# strobo.net
KiCad netlist of a schematic drawn in EAGLE
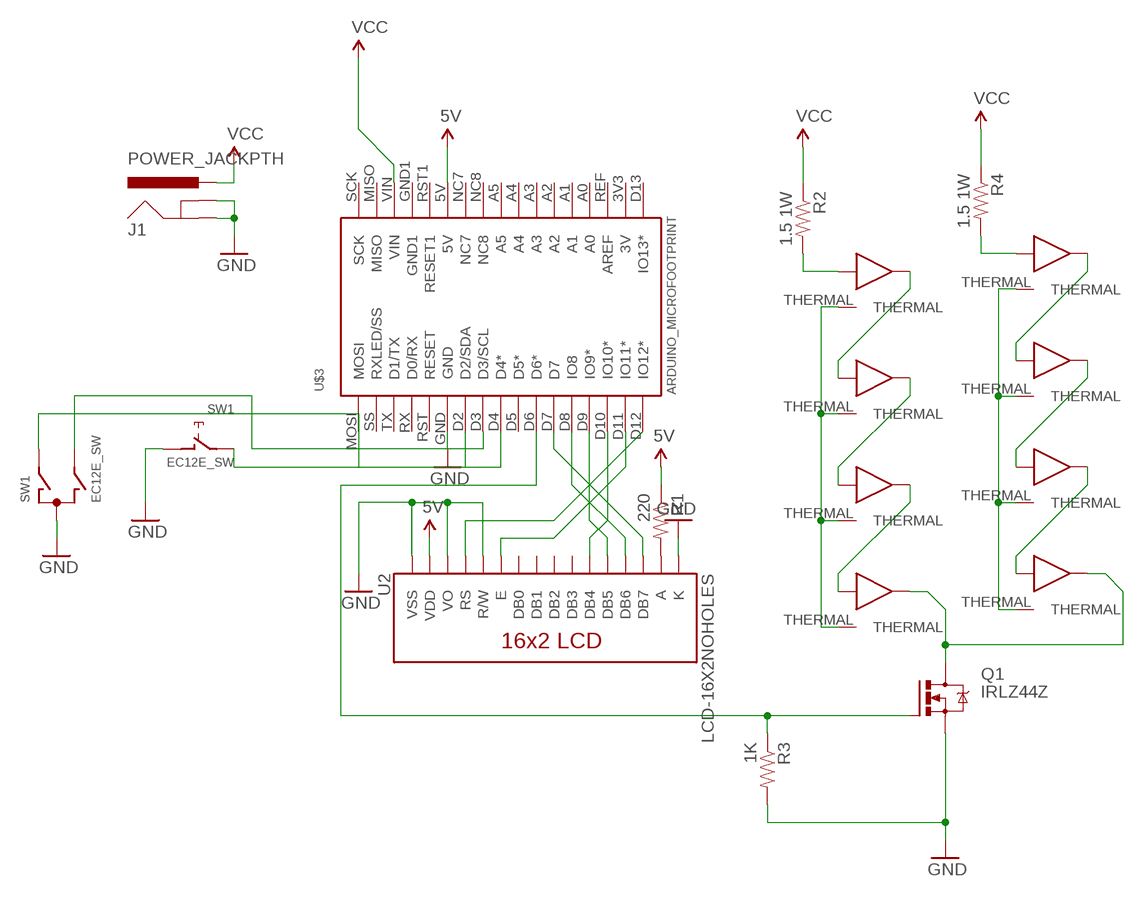
[diagram p0: schematic, sheet 1]

(export (version "E")
  (design (tool "Eeschema 10.0.6"))
  (components
    (comp (ref "J1")
      (value "POWER_JACKPTH")
      (footprint "eagle-import:POWER_JACK_PTH")
      (libsource (lib "eagle-import") (part "POWER_JACKPTH"))
    )
    (comp (ref "Q1")
      (value "IRLZ44Z")
      (footprint "eagle-import:TO220BH")
      (libsource (lib "eagle-import") (part "IRLZ44Z"))
    )
    (comp (ref "R1")
      (value "220")
      (footprint "eagle-import:AXIAL-0.4")
      (libsource (lib "eagle-import") (part "RESISTORPTH-1/4W"))
    )
    (comp (ref "R2")
      (value "1.5 1W")
      (footprint "eagle-import:AXIAL-0.4")
      (libsource (lib "eagle-import") (part "RESISTORPTH-1/4W"))
    )
    (comp (ref "R3")
      (value "1K")
      (footprint "eagle-import:AXIAL-0.4")
      (libsource (lib "eagle-import") (part "RESISTORPTH-1/4W"))
    )
    (comp (ref "R4")
      (value "1.5 1W")
      (footprint "eagle-import:AXIAL-0.4")
      (libsource (lib "eagle-import") (part "RESISTORPTH-1/4W"))
    )
    (comp (ref "SW1")
      (value "EC12E_SW")
      (footprint "eagle-import:ALPS_EC12E_SW")
      (fields (field (name "MPN") "EC12E2424407"))
      (libsource (lib "eagle-import") (part "EC12E_SW"))
    )
    (comp (ref "U$1")
      (value "LED")
      (footprint "eagle-import:LUXEONREBEL")
      (libsource (lib "eagle-import") (part "LED"))
    )
    (comp (ref "U$2")
      (value "LED")
      (footprint "eagle-import:LUXEONREBEL")
      (libsource (lib "eagle-import") (part "LED"))
    )
    (comp (ref "U$3")
      (value "ARDUINO_MICROFOOTPRINT")
      (footprint "eagle-import:ARDUINO-MICRO")
      (libsource (lib "eagle-import") (part "ARDUINO_MICROFOOTPRINT"))
    )
    (comp (ref "U$4")
      (value "LED")
      (footprint "eagle-import:LUXEONREBEL")
      (libsource (lib "eagle-import") (part "LED"))
    )
    (comp (ref "U$5")
      (value "LED")
      (footprint "eagle-import:LUXEONREBEL")
      (libsource (lib "eagle-import") (part "LED"))
    )
    (comp (ref "U$6")
      (value "LED")
      (footprint "eagle-import:LUXEONREBEL")
      (libsource (lib "eagle-import") (part "LED"))
    )
    (comp (ref "U$7")
      (value "LED")
      (footprint "eagle-import:LUXEONREBEL")
      (libsource (lib "eagle-import") (part "LED"))
    )
    (comp (ref "U$8")
      (value "LED")
      (footprint "eagle-import:LUXEONREBEL")
      (libsource (lib "eagle-import") (part "LED"))
    )
    (comp (ref "U$9")
      (value "LED")
      (footprint "eagle-import:LUXEONREBEL")
      (libsource (lib "eagle-import") (part "LED"))
    )
    (comp (ref "U2")
      (value "LCD-16X2NOHOLES")
      (footprint "eagle-import:LCD-16X2_NOHOLES")
      (libsource (lib "eagle-import") (part "LCD-16X2NOHOLES"))
    )
  )
  (nets
    (net (code "1") (name "5V") (class "Default")
      (node (ref "R1") (pin "P$1") (pinfunction "1_P$1") (pintype "passive"))
      (node (ref "U$3") (pin "5V") (pinfunction "5V_5V") (pintype "bidirectional"))
      (node (ref "U2") (pin "2") (pinfunction "VDD_2") (pintype "power_in"))
    )
    (net (code "2") (name "GND") (class "Default")
      (node (ref "J1") (pin "GND") (pinfunction "GND_GND") (pintype "bidirectional"))
      (node (ref "J1") (pin "GNDBREAK") (pinfunction "GNDBREAK_GNDBREAK") (pintype "bidirectional"))
      (node (ref "Q1") (pin "S") (pinfunction "S_S") (pintype "passive"))
      (node (ref "R3") (pin "P$2") (pinfunction "2_P$2") (pintype "passive"))
      (node (ref "SW1") (pin "C") (pinfunction "C_C") (pintype "passive"))
      (node (ref "SW1") (pin "D") (pinfunction "1_D") (pintype "passive"))
      (node (ref "U$3") (pin "GND") (pinfunction "GND_GND") (pintype "bidirectional"))
      (node (ref "U2") (pin "1") (pinfunction "VSS_1") (pintype "power_in"))
      (node (ref "U2") (pin "16") (pinfunction "K_16") (pintype "power_in"))
      (node (ref "U2") (pin "3") (pinfunction "VO_3") (pintype "bidirectional"))
      (node (ref "U2") (pin "5") (pinfunction "R/W_5") (pintype "input"))
    )
    (net (code "3") (name "Net-(Q1-PadD)") (class "Default")
      (node (ref "Q1") (pin "D") (pinfunction "D_D") (pintype "passive"))
      (node (ref "U$5") (pin "CATHODE") (pinfunction "CATHODE_CATHODE") (pintype "bidirectional"))
      (node (ref "U$9") (pin "CATHODE") (pinfunction "CATHODE_CATHODE") (pintype "bidirectional"))
    )
    (net (code "4") (name "Net-(R1-2)") (class "Default")
      (node (ref "R1") (pin "P$2") (pinfunction "2_P$2") (pintype "passive"))
      (node (ref "U2") (pin "15") (pinfunction "A_15") (pintype "power_in"))
    )
    (net (code "5") (name "Net-(R2-2)") (class "Default")
      (node (ref "R2") (pin "P$2") (pinfunction "2_P$2") (pintype "passive"))
      (node (ref "U$1") (pin "ANODE") (pinfunction "ANODE_ANODE") (pintype "bidirectional"))
    )
    (net (code "6") (name "Net-(R3-1)") (class "Default")
      (node (ref "Q1") (pin "G") (pinfunction "G_G") (pintype "passive"))
      (node (ref "R3") (pin "P$1") (pinfunction "1_P$1") (pintype "passive"))
      (node (ref "U$3") (pin "D6") (pinfunction "D6*_D6") (pintype "bidirectional"))
    )
    (net (code "7") (name "Net-(R4-2)") (class "Default")
      (node (ref "R4") (pin "P$2") (pinfunction "2_P$2") (pintype "passive"))
      (node (ref "U$6") (pin "ANODE") (pinfunction "ANODE_ANODE") (pintype "bidirectional"))
    )
    (net (code "8") (name "Net-(SW1B-2)") (class "Default")
      (node (ref "SW1") (pin "E") (pinfunction "2_E") (pintype "passive"))
      (node (ref "U$3") (pin "D4") (pinfunction "D4*_D4") (pintype "bidirectional"))
    )
    (net (code "9") (name "Net-(U$1-PadCATHODE)") (class "Default")
      (node (ref "U$1") (pin "CATHODE") (pinfunction "CATHODE_CATHODE") (pintype "bidirectional"))
      (node (ref "U$2") (pin "ANODE") (pinfunction "ANODE_ANODE") (pintype "bidirectional"))
    )
    (net (code "10") (name "Net-(U$1-PadTHERMAL)") (class "Default")
      (node (ref "U$1") (pin "THERMAL") (pinfunction "THERMAL_THERMAL") (pintype "bidirectional"))
      (node (ref "U$2") (pin "THERMAL") (pinfunction "THERMAL_THERMAL") (pintype "bidirectional"))
      (node (ref "U$4") (pin "THERMAL") (pinfunction "THERMAL_THERMAL") (pintype "bidirectional"))
      (node (ref "U$5") (pin "THERMAL") (pinfunction "THERMAL_THERMAL") (pintype "bidirectional"))
    )
    (net (code "11") (name "Net-(U$2-PadCATHODE)") (class "Default")
      (node (ref "U$2") (pin "CATHODE") (pinfunction "CATHODE_CATHODE") (pintype "bidirectional"))
      (node (ref "U$4") (pin "ANODE") (pinfunction "ANODE_ANODE") (pintype "bidirectional"))
    )
    (net (code "12") (name "Net-(U$3-D2{slash}SDA)") (class "Default")
      (node (ref "SW1") (pin "A") (pinfunction "A_A") (pintype "passive"))
      (node (ref "U$3") (pin "D2") (pinfunction "D2/SDA_D2") (pintype "bidirectional"))
    )
    (net (code "13") (name "Net-(U$3-D3{slash}SCL)") (class "Default")
      (node (ref "SW1") (pin "B") (pinfunction "B_B") (pintype "passive"))
      (node (ref "U$3") (pin "D3") (pinfunction "D3/SCL_D3") (pintype "bidirectional"))
    )
    (net (code "14") (name "Net-(U$3-IO8)") (class "Default")
      (node (ref "U$3") (pin "D8") (pinfunction "IO8_D8") (pintype "bidirectional"))
      (node (ref "U2") (pin "13") (pinfunction "DB6_13") (pintype "bidirectional"))
    )
    (net (code "15") (name "Net-(U$3-IO9*)") (class "Default")
      (node (ref "U$3") (pin "D9") (pinfunction "IO9*_D9") (pintype "bidirectional"))
      (node (ref "U2") (pin "12") (pinfunction "DB5_12") (pintype "bidirectional"))
    )
    (net (code "16") (name "Net-(U$3-IO10*)") (class "Default")
      (node (ref "U$3") (pin "D10") (pinfunction "IO10*_D10") (pintype "bidirectional"))
      (node (ref "U2") (pin "11") (pinfunction "DB4_11") (pintype "bidirectional"))
    )
    (net (code "17") (name "Net-(U$3-IO11*)") (class "Default")
      (node (ref "U$3") (pin "D11") (pinfunction "IO11*_D11") (pintype "bidirectional"))
      (node (ref "U2") (pin "6") (pinfunction "E_6") (pintype "input"))
    )
    (net (code "18") (name "Net-(U$3-IO12*)") (class "Default")
      (node (ref "U$3") (pin "D12") (pinfunction "IO12*_D12") (pintype "bidirectional"))
      (node (ref "U2") (pin "4") (pinfunction "RS_4") (pintype "input"))
    )
    (net (code "19") (name "Net-(U$4-PadCATHODE)") (class "Default")
      (node (ref "U$4") (pin "CATHODE") (pinfunction "CATHODE_CATHODE") (pintype "bidirectional"))
      (node (ref "U$5") (pin "ANODE") (pinfunction "ANODE_ANODE") (pintype "bidirectional"))
    )
    (net (code "20") (name "Net-(U$6-PadCATHODE)") (class "Default")
      (node (ref "U$6") (pin "CATHODE") (pinfunction "CATHODE_CATHODE") (pintype "bidirectional"))
      (node (ref "U$7") (pin "ANODE") (pinfunction "ANODE_ANODE") (pintype "bidirectional"))
    )
    (net (code "21") (name "Net-(U$6-PadTHERMAL)") (class "Default")
      (node (ref "U$6") (pin "THERMAL") (pinfunction "THERMAL_THERMAL") (pintype "bidirectional"))
      (node (ref "U$7") (pin "THERMAL") (pinfunction "THERMAL_THERMAL") (pintype "bidirectional"))
      (node (ref "U$8") (pin "THERMAL") (pinfunction "THERMAL_THERMAL") (pintype "bidirectional"))
      (node (ref "U$9") (pin "THERMAL") (pinfunction "THERMAL_THERMAL") (pintype "bidirectional"))
    )
    (net (code "22") (name "Net-(U$7-PadCATHODE)") (class "Default")
      (node (ref "U$7") (pin "CATHODE") (pinfunction "CATHODE_CATHODE") (pintype "bidirectional"))
      (node (ref "U$8") (pin "ANODE") (pinfunction "ANODE_ANODE") (pintype "bidirectional"))
    )
    (net (code "23") (name "Net-(U$8-PadCATHODE)") (class "Default")
      (node (ref "U$8") (pin "CATHODE") (pinfunction "CATHODE_CATHODE") (pintype "bidirectional"))
      (node (ref "U$9") (pin "ANODE") (pinfunction "ANODE_ANODE") (pintype "bidirectional"))
    )
    (net (code "24") (name "Net-(U2-DB7)") (class "Default")
      (node (ref "U$3") (pin "D7") (pinfunction "D7_D7") (pintype "bidirectional"))
      (node (ref "U2") (pin "14") (pinfunction "DB7_14") (pintype "bidirectional"))
    )
    (net (code "25") (name "VCC") (class "Default")
      (node (ref "J1") (pin "PWR") (pinfunction "PWR_PWR") (pintype "bidirectional"))
      (node (ref "R2") (pin "P$1") (pinfunction "1_P$1") (pintype "passive"))
      (node (ref "R4") (pin "P$1") (pinfunction "1_P$1") (pintype "passive"))
      (node (ref "U$3") (pin "VIN") (pinfunction "VIN_VIN") (pintype "bidirectional"))
    )
    (net (code "26") (name "unconnected-(U$3-3V-Pad3V3)") (class "Default")
      (node (ref "U$3") (pin "3V3") (pinfunction "3V_3V3") (pintype "bidirectional"))
    )
    (net (code "27") (name "unconnected-(U$3-AREF-PadREF)") (class "Default")
      (node (ref "U$3") (pin "REF") (pinfunction "AREF_REF") (pintype "bidirectional"))
    )
    (net (code "28") (name "unconnected-(U$3-D0{slash}RX-PadRX)") (class "Default")
      (node (ref "U$3") (pin "RX") (pinfunction "D0/RX_RX") (pintype "bidirectional"))
    )
    (net (code "29") (name "unconnected-(U$3-D1{slash}TX-PadTX)") (class "Default")
      (node (ref "U$3") (pin "TX") (pinfunction "D1/TX_TX") (pintype "bidirectional"))
    )
    (net (code "30") (name "unconnected-(U$3-D5*-PadD5)") (class "Default")
      (node (ref "U$3") (pin "D5") (pinfunction "D5*_D5") (pintype "bidirectional"))
    )
    (net (code "31") (name "unconnected-(U$3-IO13*-PadD13)") (class "Default")
      (node (ref "U$3") (pin "D13") (pinfunction "IO13*_D13") (pintype "bidirectional"))
    )
    (net (code "32") (name "unconnected-(U$3-PadA0)") (class "Default")
      (node (ref "U$3") (pin "A0") (pinfunction "A0_A0") (pintype "bidirectional"))
    )
    (net (code "33") (name "unconnected-(U$3-PadA1)") (class "Default")
      (node (ref "U$3") (pin "A1") (pinfunction "A1_A1") (pintype "bidirectional"))
    )
    (net (code "34") (name "unconnected-(U$3-PadA2)") (class "Default")
      (node (ref "U$3") (pin "A2") (pinfunction "A2_A2") (pintype "bidirectional"))
    )
    (net (code "35") (name "unconnected-(U$3-PadA3)") (class "Default")
      (node (ref "U$3") (pin "A3") (pinfunction "A3_A3") (pintype "bidirectional"))
    )
    (net (code "36") (name "unconnected-(U$3-PadA4)") (class "Default")
      (node (ref "U$3") (pin "A4") (pinfunction "A4_A4") (pintype "bidirectional"))
    )
    (net (code "37") (name "unconnected-(U$3-PadA5)") (class "Default")
      (node (ref "U$3") (pin "A5") (pinfunction "A5_A5") (pintype "bidirectional"))
    )
    (net (code "38") (name "unconnected-(U$3-PadGND1)") (class "Default")
      (node (ref "U$3") (pin "GND1") (pinfunction "GND1_GND1") (pintype "bidirectional"))
    )
    (net (code "39") (name "unconnected-(U$3-PadMISO)") (class "Default")
      (node (ref "U$3") (pin "MISO") (pinfunction "MISO_MISO") (pintype "bidirectional"))
    )
    (net (code "40") (name "unconnected-(U$3-PadMOSI)") (class "Default")
      (node (ref "U$3") (pin "MOSI") (pinfunction "MOSI_MOSI") (pintype "bidirectional"))
    )
    (net (code "41") (name "unconnected-(U$3-PadNC7)") (class "Default")
      (node (ref "U$3") (pin "NC7") (pinfunction "NC7_NC7") (pintype "bidirectional"))
    )
    (net (code "42") (name "unconnected-(U$3-PadNC8)") (class "Default")
      (node (ref "U$3") (pin "NC8") (pinfunction "NC8_NC8") (pintype "bidirectional"))
    )
    (net (code "43") (name "unconnected-(U$3-PadSCK)") (class "Default")
      (node (ref "U$3") (pin "SCK") (pinfunction "SCK_SCK") (pintype "bidirectional"))
    )
    (net (code "44") (name "unconnected-(U$3-RESET-PadRST)") (class "Default")
      (node (ref "U$3") (pin "RST") (pinfunction "RESET_RST") (pintype "bidirectional"))
    )
    (net (code "45") (name "unconnected-(U$3-RESET1-PadRST1)") (class "Default")
      (node (ref "U$3") (pin "RST1") (pinfunction "RESET1_RST1") (pintype "bidirectional"))
    )
    (net (code "46") (name "unconnected-(U$3-RXLED{slash}SS-PadSS)") (class "Default")
      (node (ref "U$3") (pin "SS") (pinfunction "RXLED/SS_SS") (pintype "bidirectional"))
    )
    (net (code "47") (name "unconnected-(U2-DB0-Pad7)") (class "Default")
      (node (ref "U2") (pin "7") (pinfunction "DB0_7") (pintype "bidirectional"))
    )
    (net (code "48") (name "unconnected-(U2-DB1-Pad8)") (class "Default")
      (node (ref "U2") (pin "8") (pinfunction "DB1_8") (pintype "bidirectional"))
    )
    (net (code "49") (name "unconnected-(U2-DB2-Pad9)") (class "Default")
      (node (ref "U2") (pin "9") (pinfunction "DB2_9") (pintype "bidirectional"))
    )
    (net (code "50") (name "unconnected-(U2-DB3-Pad10)") (class "Default")
      (node (ref "U2") (pin "10") (pinfunction "DB3_10") (pintype "bidirectional"))
    )
  )
)
